# soloar_Power.net
KiCad netlist of a schematic drawn in EAGLE
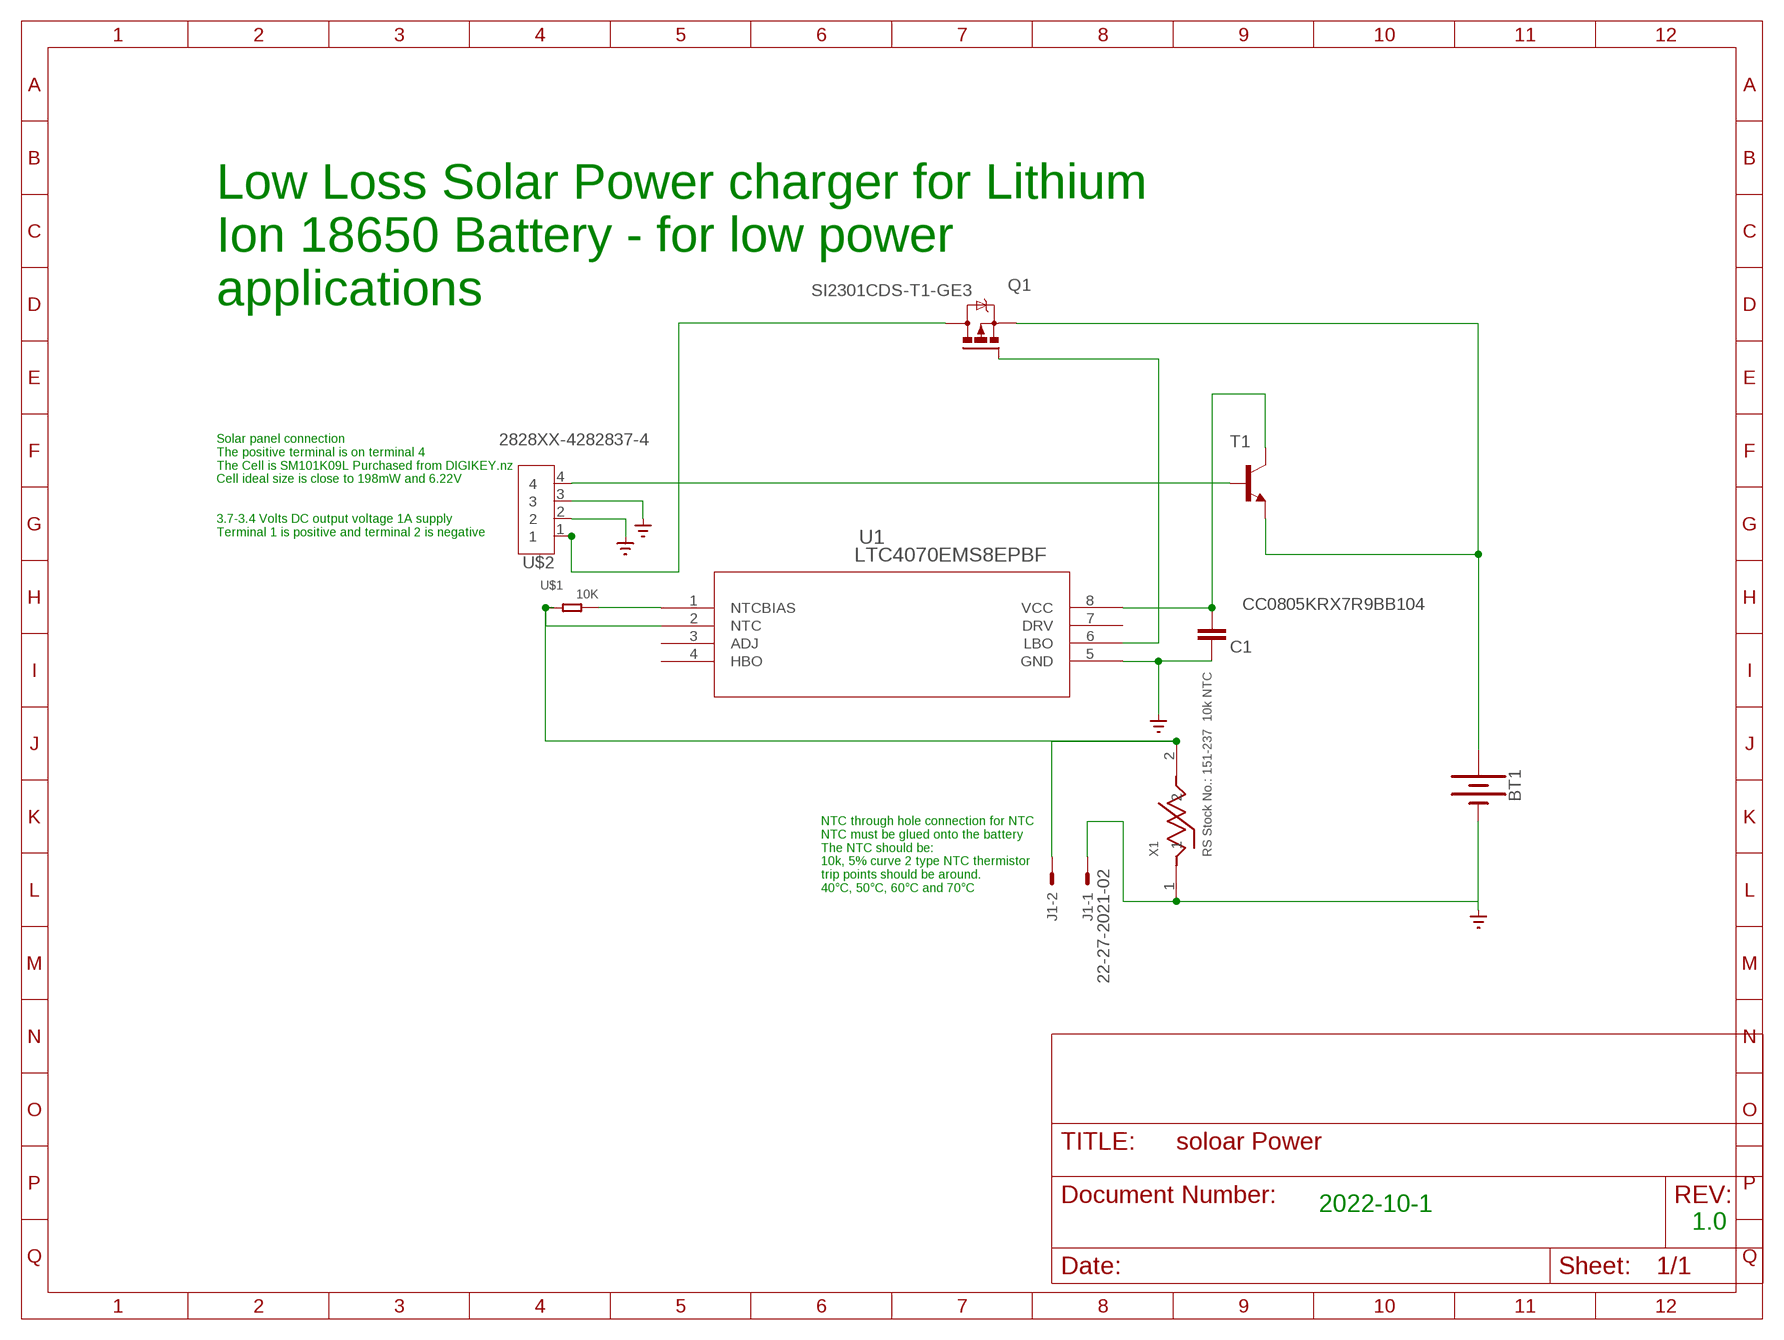
[diagram p0: schematic, sheet 1]

(export (version "E")
  (design (tool "Eeschema 10.0.6"))
  (components
    (comp (ref "BT1")
      (value "BATTERY-18650")
      (footprint "eagle-import:BATTERY_18650-HOLDER")
      (libsource (lib "eagle-import") (part "BATTERY-18650"))
    )
    (comp (ref "C1")
      (value "CC0805KRX7R9BB104")
      (footprint "eagle-import:CAP_0805")
      (fields
        (field (name "DIGIKEY_PART_NUMBER") "311-1140-2-ND")
        (field (name "MANUFACTURER") "Yageo")
        (field (name "CREATED_BY") "PCBLayout.com")
      )
      (libsource (lib "eagle-import") (part "CC0805KRX7R9BB104"))
    )
    (comp (ref "J1")
      (value "22-27-2021-02")
      (footprint "eagle-import:6410-02")
      (fields (field (name "MF") "MOLEX"))
      (libsource (lib "eagle-import") (part "22-?-0227-2021"))
    )
    (comp (ref "Q1")
      (value "SI2301CDS-T1-GE3")
      (footprint "eagle-import:SOT23")
      (libsource (lib "eagle-import") (part "PMOSFET_SOT23_"))
    )
    (comp (ref "T1")
      (value "MMBT3904LT1-NPN-SOT23-BEC")
      (footprint "eagle-import:SOT23-BEC")
      (libsource (lib "eagle-import") (part "-NPN-SOT23-BECMMBT3904LT1"))
    )
    (comp (ref "U$1")
      (value "10K")
      (footprint "eagle-import:R0805")
      (fields (field (name "MPN") "RC0805FR-0710KL"))
      (libsource (lib "eagle-import") (part "SMD-RES-10K-1%-1/8W(0805)"))
    )
    (comp (ref "U$2")
      (value "2828XX-4282837-4")
      (footprint "eagle-import:TERMBLK_508-4N")
      (fields (field (name "MANUFACTURER") "TE Connectivity") (field (name "MPN") "282837-4"))
      (libsource (lib "eagle-import") (part "2828XX-4282837-4"))
    )
    (comp (ref "U1")
      (value "LTC4070EMS8EPBF")
      (footprint "eagle-import:MSOP-8_MS")
      (fields (field (name "MF") "Analog Devices") (field (name "MP") "LTC4070EMS8E#PBF"))
      (libsource (lib "eagle-import") (part "LTC4070EMS8EPBF"))
    )
    (comp (ref "X1")
      (value "RS Stock No.: 151-237  10k NTC")
      (footprint "eagle-import:NCP18WF104J03RB")
      (fields
        (field (name "DIGIKEY_PART_NUMBER") "490-2430-2-ND")
        (field (name "MANUFACTURER") "Murata Electronics North America")
        (field (name "MPN") "NCP18WF104J03RB")
        (field (name "CREATED_BY") "PCBLayout.com")
      )
      (libsource (lib "eagle-import") (part "NCP18WF104J03RB"))
    )
  )
  (nets
    (net (code "1") (name "Net-(BT1-+)") (class "Default")
      (node (ref "BT1") (pin "PWR@1") (pinfunction "+_PWR@1") (pintype "power_in"))
      (node (ref "Q1") (pin "2") (pinfunction "S_2") (pintype "passive"))
      (node (ref "T1") (pin "E") (pinfunction "E_E") (pintype "passive"))
    )
    (net (code "2") (name "Net-(J1B-S)") (class "Default")
      (node (ref "J1") (pin "2") (pinfunction "S_2") (pintype "passive"))
      (node (ref "U$1") (pin "2") (pinfunction "2_2") (pintype "passive"))
      (node (ref "U1") (pin "2") (pinfunction "NTC_2") (pintype "passive"))
      (node (ref "X1") (pin "2") (pinfunction "2_2") (pintype "passive"))
    )
    (net (code "3") (name "Net-(Q1-D)") (class "Default")
      (node (ref "Q1") (pin "3") (pinfunction "D_3") (pintype "passive"))
      (node (ref "U$2") (pin "1") (pinfunction "1_1") (pintype "bidirectional"))
    )
    (net (code "4") (name "Net-(Q1-G)") (class "Default")
      (node (ref "Q1") (pin "1") (pinfunction "G_1") (pintype "passive"))
      (node (ref "U1") (pin "6") (pinfunction "LBO_6") (pintype "output"))
    )
    (net (code "5") (name "Net-(T1-PadB)") (class "Default")
      (node (ref "T1") (pin "B") (pinfunction "B_B") (pintype "passive"))
      (node (ref "U$2") (pin "4") (pinfunction "4_4") (pintype "bidirectional"))
    )
    (net (code "6") (name "Net-(U1-NTCBIAS)") (class "Default")
      (node (ref "U$1") (pin "1") (pinfunction "1_1") (pintype "passive"))
      (node (ref "U1") (pin "1") (pinfunction "NTCBIAS_1") (pintype "passive"))
    )
    (net (code "7") (name "Net-(U1-VCC)") (class "Default")
      (node (ref "C1") (pin "1") (pinfunction "1_1") (pintype "passive"))
      (node (ref "T1") (pin "C") (pinfunction "C_C") (pintype "passive"))
      (node (ref "U1") (pin "8") (pinfunction "VCC_8") (pintype "power_in"))
    )
    (net (code "8") (name "SUPPLY0_GND_") (class "Default")
      (node (ref "BT1") (pin "GND@1") (pinfunction "-_GND@1") (pintype "power_in"))
      (node (ref "C1") (pin "2") (pinfunction "2_2") (pintype "passive"))
      (node (ref "J1") (pin "1") (pinfunction "S_1") (pintype "passive"))
      (node (ref "U$2") (pin "2") (pinfunction "2_2") (pintype "bidirectional"))
      (node (ref "U$2") (pin "3") (pinfunction "3_3") (pintype "bidirectional"))
      (node (ref "U1") (pin "5") (pinfunction "GND_5") (pintype "power_in"))
      (node (ref "X1") (pin "1") (pinfunction "1_1") (pintype "passive"))
    )
    (net (code "9") (name "unconnected-(U1-ADJ-Pad3)") (class "Default")
      (node (ref "U1") (pin "3") (pinfunction "ADJ_3") (pintype "passive"))
    )
    (net (code "10") (name "unconnected-(U1-DRV-Pad7)") (class "Default")
      (node (ref "U1") (pin "7") (pinfunction "DRV_7") (pintype "output"))
    )
    (net (code "11") (name "unconnected-(U1-HBO-Pad4)") (class "Default")
      (node (ref "U1") (pin "4") (pinfunction "HBO_4") (pintype "output"))
    )
  )
)
